# HealthMonitor.net
KiCad netlist of a schematic drawn in EAGLE
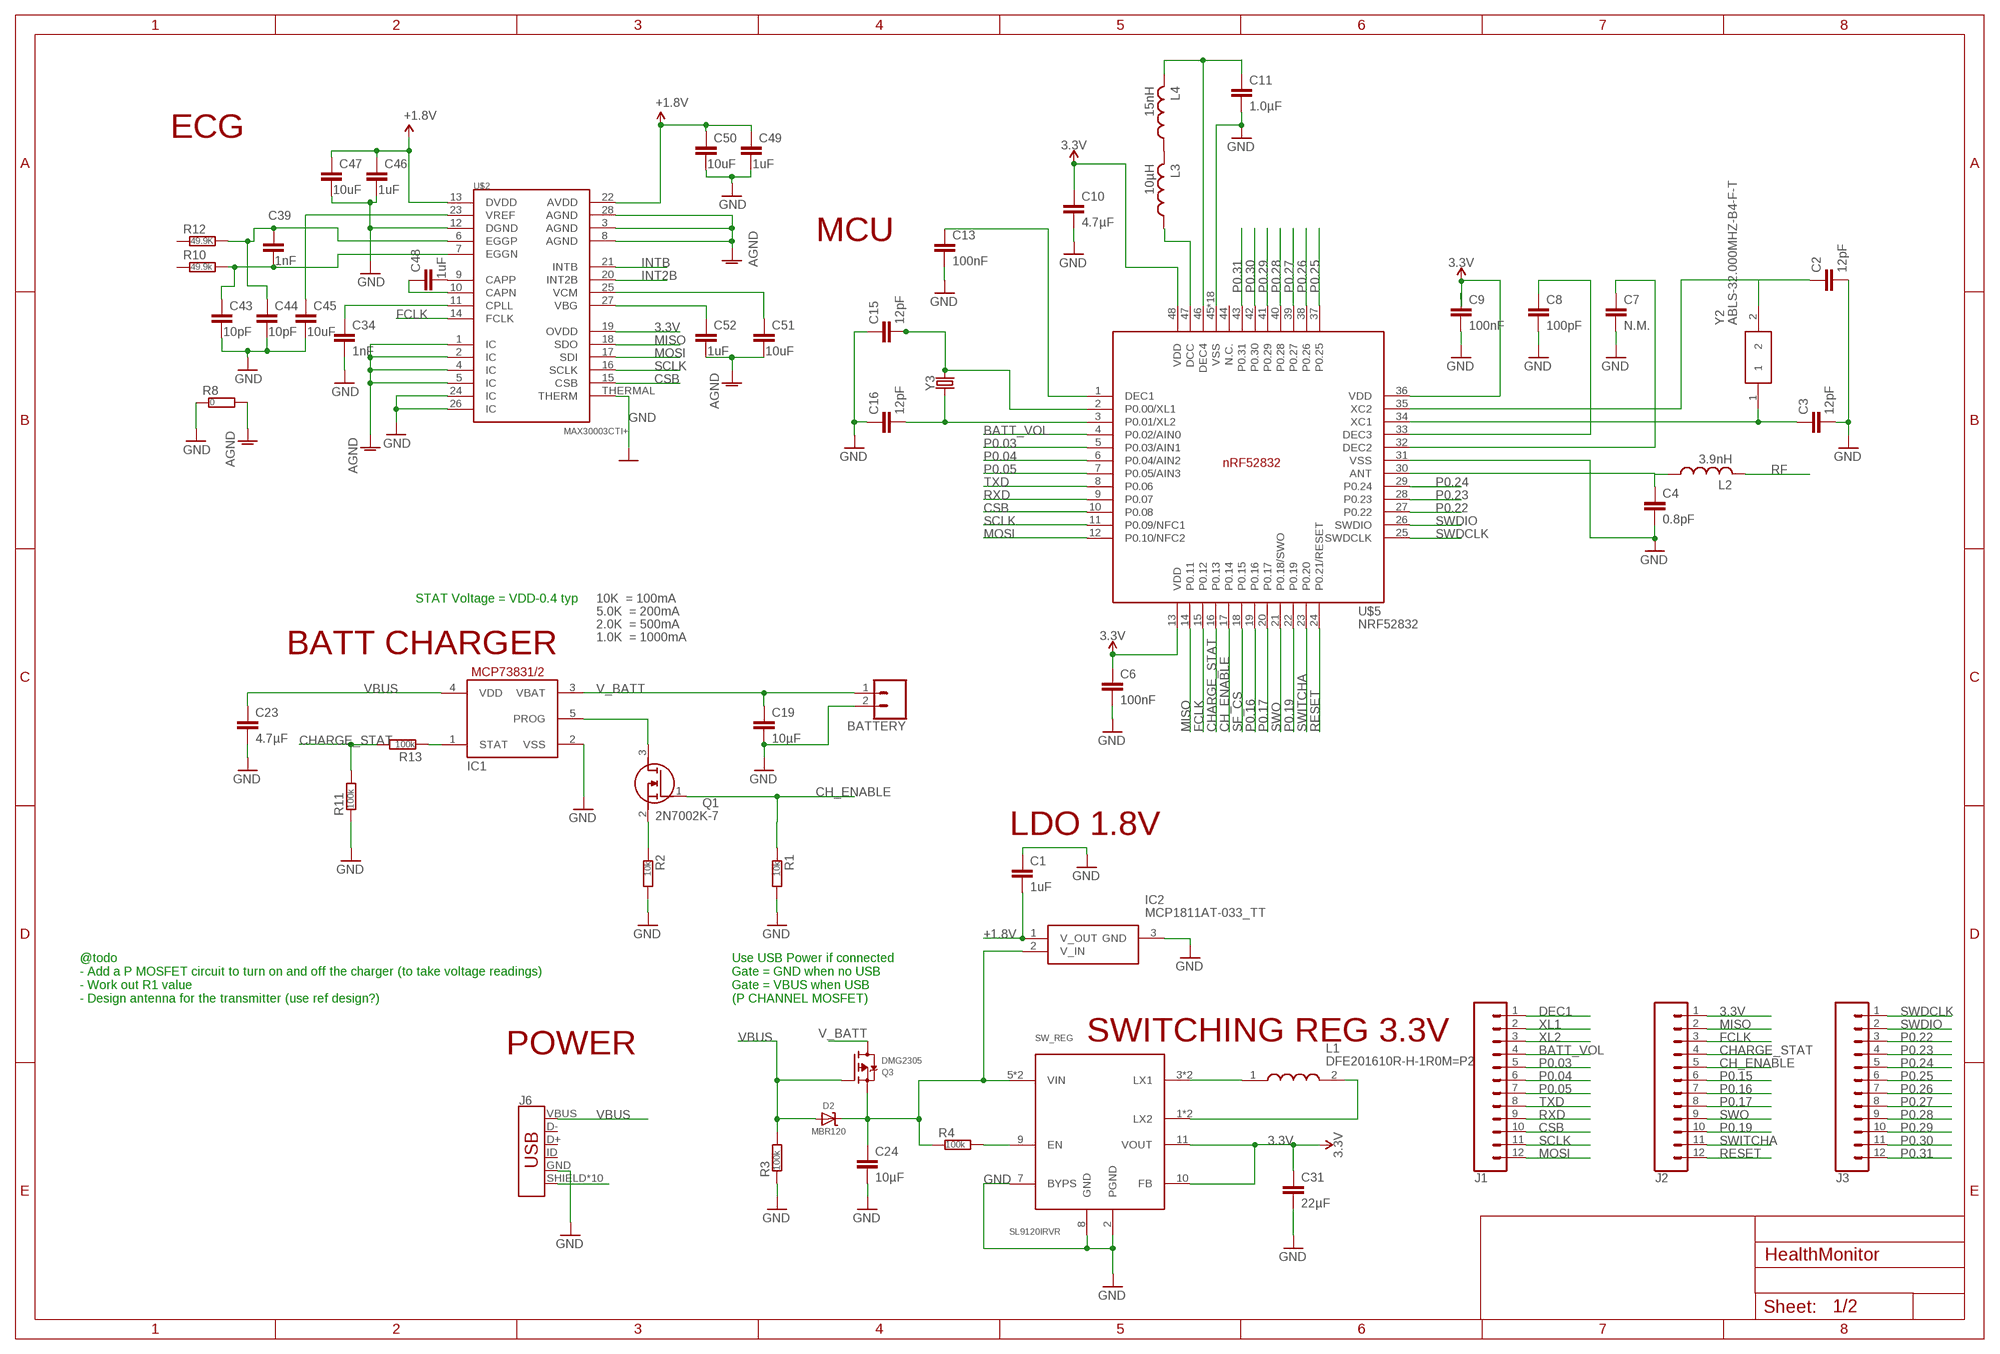
[diagram p0: schematic, sheet 1]
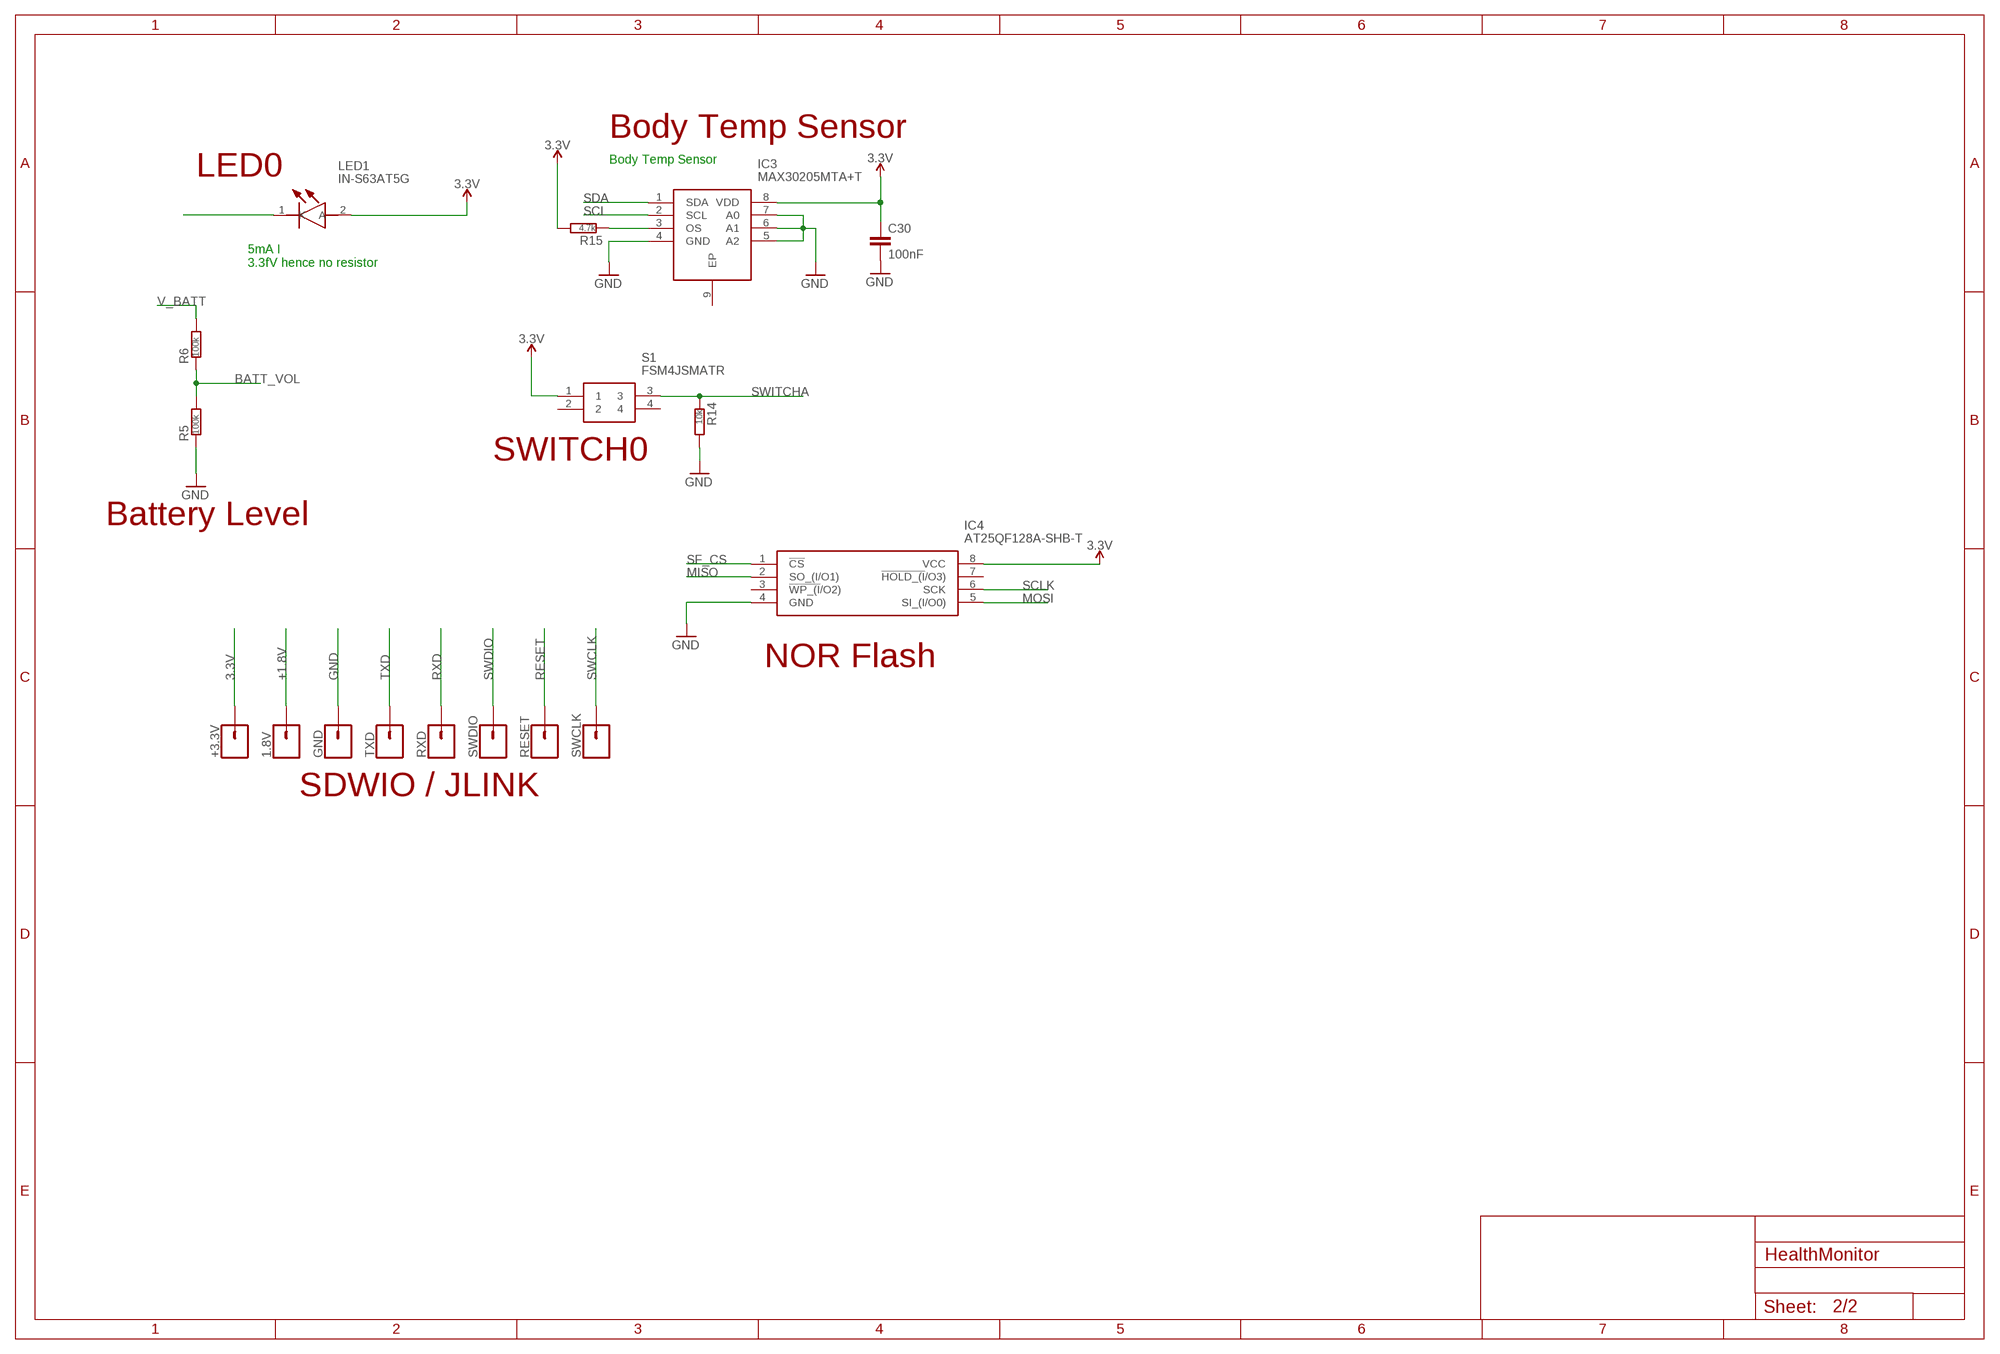
[diagram p1: schematic, sheet 2]

(export (version "E")
  (design (tool "Eeschema 10.0.6"))
  (components
    (comp (ref "BATTERY")
      (value "CONN_02")
      (footprint "eagle-import:1X02")
      (libsource (lib "eagle-import") (part "CONN_02"))
    )
    (comp (ref "C1")
      (value "1uF")
      (footprint "eagle-import:RESC0603_L")
      (libsource (lib "eagle-import") (part "CAPACITOR_0603_L"))
    )
    (comp (ref "C2")
      (value "12pF")
      (footprint "eagle-import:RESC0603_L")
      (libsource (lib "eagle-import") (part "CAPACITOR_0603_L"))
    )
    (comp (ref "C3")
      (value "12pF")
      (footprint "eagle-import:RESC0603_L")
      (libsource (lib "eagle-import") (part "CAPACITOR_0603_L"))
    )
    (comp (ref "C4")
      (value "0.8pF")
      (footprint "eagle-import:RESC0603_L")
      (libsource (lib "eagle-import") (part "CAPACITOR_0603_L"))
    )
    (comp (ref "C6")
      (value "100nF")
      (footprint "eagle-import:RESC0603_L")
      (libsource (lib "eagle-import") (part "CAPACITOR_0603_L"))
    )
    (comp (ref "C7")
      (value "N.M.")
      (footprint "eagle-import:RESC0603_L")
      (libsource (lib "eagle-import") (part "CAPACITOR_0603_L"))
    )
    (comp (ref "C8")
      (value "100pF")
      (footprint "eagle-import:RESC0603_L")
      (libsource (lib "eagle-import") (part "CAPACITOR_0603_L"))
    )
    (comp (ref "C9")
      (value "100nF")
      (footprint "eagle-import:RESC0603_L")
      (libsource (lib "eagle-import") (part "CAPACITOR_0603_L"))
    )
    (comp (ref "C10")
      (value "4.7µF")
      (footprint "eagle-import:RESC0603_N")
      (libsource (lib "eagle-import") (part "CAPACITOR_0603_N"))
    )
    (comp (ref "C11")
      (value "1.0µF")
      (footprint "eagle-import:RESC0603_N")
      (libsource (lib "eagle-import") (part "CAPACITOR_0603_N"))
    )
    (comp (ref "C13")
      (value "100nF")
      (footprint "eagle-import:RESC0603_L")
      (libsource (lib "eagle-import") (part "CAPACITOR_0603_L"))
    )
    (comp (ref "C15")
      (value "12pF")
      (footprint "eagle-import:RESC0603_L")
      (libsource (lib "eagle-import") (part "CAPACITOR_0603_L"))
    )
    (comp (ref "C16")
      (value "12pF")
      (footprint "eagle-import:RESC0603_L")
      (libsource (lib "eagle-import") (part "CAPACITOR_0603_L"))
    )
    (comp (ref "C19")
      (value "10µF")
      (footprint "eagle-import:RESC0603_N")
      (libsource (lib "eagle-import") (part "CAPACITOR_0603_N"))
    )
    (comp (ref "C23")
      (value "4.7µF")
      (footprint "eagle-import:RESC0603_N")
      (libsource (lib "eagle-import") (part "CAPACITOR_0603_N"))
    )
    (comp (ref "C24")
      (value "10µF")
      (footprint "eagle-import:RESC0603_N")
      (libsource (lib "eagle-import") (part "CAPACITOR_0603_N"))
    )
    (comp (ref "C31")
      (value "22µF")
      (footprint "eagle-import:RESC0603_N")
      (libsource (lib "eagle-import") (part "CAPACITOR_0603_N"))
    )
    (comp (ref "C34")
      (value "1nF")
      (footprint "eagle-import:C0603")
      (libsource (lib "eagle-import") (part "C-EUC0603"))
    )
    (comp (ref "C39")
      (value "1nF")
      (footprint "eagle-import:RESC0603_N")
      (libsource (lib "eagle-import") (part "CAPACITOR_0603_N"))
    )
    (comp (ref "C43")
      (value "10pF")
      (footprint "eagle-import:RESC0603_N")
      (libsource (lib "eagle-import") (part "CAPACITOR_0603_N"))
    )
    (comp (ref "C44")
      (value "10pF")
      (footprint "eagle-import:RESC0603_N")
      (libsource (lib "eagle-import") (part "CAPACITOR_0603_N"))
    )
    (comp (ref "C45")
      (value "10uF")
      (footprint "eagle-import:RESC0603_N")
      (libsource (lib "eagle-import") (part "CAPACITOR_0603_N"))
    )
    (comp (ref "C46")
      (value "1uF")
      (footprint "eagle-import:RESC0603_N")
      (libsource (lib "eagle-import") (part "CAPACITOR_0603_N"))
    )
    (comp (ref "C47")
      (value "10uF")
      (footprint "eagle-import:RESC0603_N")
      (libsource (lib "eagle-import") (part "CAPACITOR_0603_N"))
    )
    (comp (ref "C48")
      (value "1uF")
      (footprint "eagle-import:RESC0603_N")
      (libsource (lib "eagle-import") (part "CAPACITOR_0603_N"))
    )
    (comp (ref "C49")
      (value "1uF")
      (footprint "eagle-import:RESC0603_N")
      (libsource (lib "eagle-import") (part "CAPACITOR_0603_N"))
    )
    (comp (ref "C50")
      (value "10uF")
      (footprint "eagle-import:RESC0603_N")
      (libsource (lib "eagle-import") (part "CAPACITOR_0603_N"))
    )
    (comp (ref "C51")
      (value "10uF")
      (footprint "eagle-import:RESC0603_N")
      (libsource (lib "eagle-import") (part "CAPACITOR_0603_N"))
    )
    (comp (ref "C52")
      (value "1uF")
      (footprint "eagle-import:RESC0603_N")
      (libsource (lib "eagle-import") (part "CAPACITOR_0603_N"))
    )
    (comp (ref "D2")
      (value "MBR120")
      (footprint "eagle-import:SOD-123")
      (libsource (lib "eagle-import") (part "DIODE-SCHOTTKYSOD-123"))
    )
    (comp (ref "IC1")
      (value "MCP73831/OT")
      (footprint "eagle-import:SOT23-5L")
      (libsource (lib "eagle-import") (part "MCP73831/OT"))
    )
    (comp (ref "IC2")
      (value "MCP1811AT-033_TT")
      (footprint "eagle-import:SOT95P237X112-3N")
      (fields
        (field (name "MANUFACTURER_PART_NUMBER") "MCP1811AT-033/TT")
        (field (name "MOUSER_PART_NUMBER") "579-MCP1811AT-033/TT")
      )
      (libsource (lib "eagle-import") (part "MCP1811AT-033_TT"))
    )
    (comp (ref "J1")
      (value "CONN_12")
      (footprint "eagle-import:1X12")
      (libsource (lib "eagle-import") (part "CONN_12"))
    )
    (comp (ref "J2")
      (value "CONN_12")
      (footprint "eagle-import:1X12")
      (libsource (lib "eagle-import") (part "CONN_12"))
    )
    (comp (ref "J3")
      (value "CONN_12")
      (footprint "eagle-import:1X12")
      (libsource (lib "eagle-import") (part "CONN_12"))
    )
    (comp (ref "J6")
      (value "USB_MICRO-B_HALF_PTH_MILL")
      (footprint "eagle-import:USB-MICROB-PTH-MILL")
      (libsource (lib "eagle-import") (part "USB_MICRO-B_HALF_PTH_MILL"))
    )
    (comp (ref "L1")
      (value "DFE201610R-H-1R0M=P2")
      (footprint "eagle-import:INDC2016X100N")
      (fields (field (name "MOUSER_PART_NUMBER") "81-DFE201610RH1R0MP2"))
      (libsource (lib "eagle-import") (part "DFE201610R-H-1R0M=P2"))
    )
    (comp (ref "L2")
      (value "3.9nH")
      (footprint "eagle-import:RESC0402_N")
      (libsource (lib "eagle-import") (part "INDUCTOR_0402_N"))
    )
    (comp (ref "L3")
      (value "10µH")
      (footprint "eagle-import:RESC0603_N")
      (libsource (lib "eagle-import") (part "INDUCTOR_0603_N"))
    )
    (comp (ref "L4")
      (value "15nH")
      (footprint "eagle-import:RESC0402_N")
      (libsource (lib "eagle-import") (part "INDUCTOR_0402_N"))
    )
    (comp (ref "Q1")
      (value "2N7002K-7")
      (footprint "eagle-import:SOT96P240X100-3N")
      (fields (field (name "MOUSER_PART_NUMBER") "621-2N7002K-7") (field (name "RS_PART_NUMBER") "7703383"))
      (libsource (lib "eagle-import") (part "2N7002K-7"))
    )
    (comp (ref "Q3")
      (value "DMG2305")
      (footprint "eagle-import:SOT23-R")
      (libsource (lib "eagle-import") (part "MOSFET-P"))
    )
    (comp (ref "R1")
      (value "10k")
      (footprint "eagle-import:RESC0603_L")
      (libsource (lib "eagle-import") (part "RESISTOR_0603_L"))
    )
    (comp (ref "R2")
      (value "10k")
      (footprint "eagle-import:RESC0603_L")
      (libsource (lib "eagle-import") (part "RESISTOR_0603_L"))
    )
    (comp (ref "R3")
      (value "100k")
      (footprint "eagle-import:RESC0603_L")
      (libsource (lib "eagle-import") (part "RESISTOR_0603_L"))
    )
    (comp (ref "R4")
      (value "100k")
      (footprint "eagle-import:RESC0603_L")
      (libsource (lib "eagle-import") (part "RESISTOR_0603_L"))
    )
    (comp (ref "R8")
      (value "0")
      (footprint "eagle-import:RESC0603_L")
      (libsource (lib "eagle-import") (part "RESISTOR_0603_L"))
    )
    (comp (ref "R10")
      (value "49.9k")
      (footprint "eagle-import:RESC0603_L")
      (libsource (lib "eagle-import") (part "RESISTOR_0603_L"))
    )
    (comp (ref "R11")
      (value "100k")
      (footprint "eagle-import:RESC0603_L")
      (libsource (lib "eagle-import") (part "RESISTOR_0603_L"))
    )
    (comp (ref "R12")
      (value "49.9K")
      (footprint "eagle-import:RESC0603_L")
      (libsource (lib "eagle-import") (part "RESISTOR_0603_L"))
    )
    (comp (ref "R13")
      (value "100k")
      (footprint "eagle-import:RESC0603_L")
      (libsource (lib "eagle-import") (part "RESISTOR_0603_L"))
    )
    (comp (ref "SW_REG")
      (value "SL9120IRVR")
      (footprint "eagle-import:TQFN-12")
      (libsource (lib "eagle-import") (part "SL9120IRVR"))
    )
    (comp (ref "U$2")
      (value "MAX30003CTI+")
      (footprint "eagle-import:QFN-28")
      (libsource (lib "eagle-import") (part "MAX30003"))
    )
    (comp (ref "U$5")
      (value "NRF52832")
      (footprint "eagle-import:QFN40P600X600X90-48_N")
      (libsource (lib "eagle-import") (part "NRF52832"))
    )
    (comp (ref "Y2")
      (value "ABLS-32.000MHZ-B4-F-T")
      (footprint "eagle-import:ABLS-12.000MHZ-B2")
      (fields (field (name "MOUSER_PART_NUMBER") "815-ABLS-32.0MF-T"))
      (libsource (lib "eagle-import") (part "ABLS-32.000MHZ-B4-F-T"))
    )
    (comp (ref "Y3")
      (value "CRYSTALSMD-2X6")
      (footprint "eagle-import:CRYSTAL-SMD-2X6-CYL")
      (libsource (lib "eagle-import") (part "CRYSTALSMD-2X6"))
    )
    (comp (ref "+3.3V")
      (value "CONN_01")
      (footprint "eagle-import:1X01")
      (libsource (lib "eagle-import") (part "CONN_01"))
    )
    (comp (ref "1.8V")
      (value "CONN_01")
      (footprint "eagle-import:1X01")
      (libsource (lib "eagle-import") (part "CONN_01"))
    )
    (comp (ref "C30")
      (value "100nF")
      (footprint "eagle-import:RESC0603_L")
      (libsource (lib "eagle-import") (part "CAPACITOR_0603_L"))
    )
    (comp (ref "GND")
      (value "CONN_01")
      (footprint "eagle-import:1X01")
      (libsource (lib "eagle-import") (part "CONN_01"))
    )
    (comp (ref "IC3")
      (value "MAX30205MTA+T")
      (footprint "eagle-import:SON65P300X300X80-9N")
      (fields (field (name "MOUSER_PART_NUMBER") "700-MAX30205MTA+T"))
      (libsource (lib "eagle-import") (part "MAX30205MTA+T"))
    )
    (comp (ref "IC4")
      (value "AT25QF128A-SHB-T")
      (footprint "eagle-import:SOIC127P790X216-8N")
      (fields (field (name "MOUSER_PART_NUMBER") "988-AT25QF128A-SHB-T"))
      (libsource (lib "eagle-import") (part "AT25QF128A-SHB-T"))
    )
    (comp (ref "LED1")
      (value "IN-S63AT5G")
      (footprint "eagle-import:LEDM168X39N")
      (fields (field (name "MOUSER_PART_NUMBER") "743-IN-S63AT5G"))
      (libsource (lib "eagle-import") (part "IN-S63AT5G"))
    )
    (comp (ref "R5")
      (value "100k")
      (footprint "eagle-import:RESC0603_L")
      (libsource (lib "eagle-import") (part "RESISTOR_0603_L"))
    )
    (comp (ref "R6")
      (value "100k")
      (footprint "eagle-import:RESC0603_L")
      (libsource (lib "eagle-import") (part "RESISTOR_0603_L"))
    )
    (comp (ref "R14")
      (value "10k")
      (footprint "eagle-import:RESC0603_L")
      (libsource (lib "eagle-import") (part "RESISTOR_0603_L"))
    )
    (comp (ref "R15")
      (value "4.7k")
      (footprint "eagle-import:RESC0603_L")
      (libsource (lib "eagle-import") (part "RESISTOR_0603_L"))
    )
    (comp (ref "RESET")
      (value "CONN_01")
      (footprint "eagle-import:1X01")
      (libsource (lib "eagle-import") (part "CONN_01"))
    )
    (comp (ref "RXD")
      (value "CONN_01")
      (footprint "eagle-import:1X01")
      (libsource (lib "eagle-import") (part "CONN_01"))
    )
    (comp (ref "S1")
      (value "FSM4JSMATR")
      (footprint "eagle-import:FSM4JSMATR")
      (fields (field (name "MOUSER_PART_NUMBER") "506-FSM4JSMATR") (field (name "RS_PART_NUMBER") "7182455P"))
      (libsource (lib "eagle-import") (part "FSM4JSMATR"))
    )
    (comp (ref "SWCLK")
      (value "CONN_01")
      (footprint "eagle-import:1X01")
      (libsource (lib "eagle-import") (part "CONN_01"))
    )
    (comp (ref "SWDIO")
      (value "CONN_01")
      (footprint "eagle-import:1X01")
      (libsource (lib "eagle-import") (part "CONN_01"))
    )
    (comp (ref "TXD")
      (value "CONN_01")
      (footprint "eagle-import:1X01")
      (libsource (lib "eagle-import") (part "CONN_01"))
    )
  )
  (nets
    (net (code "1") (name "+1.8V") (class "Default")
      (node (ref "1.8V") (pin "1") (pinfunction "1_1") (pintype "passive"))
      (node (ref "C1") (pin "2") (pinfunction "2_2") (pintype "passive"))
      (node (ref "C46") (pin "1") (pinfunction "1_1") (pintype "passive"))
      (node (ref "C47") (pin "1") (pinfunction "1_1") (pintype "passive"))
      (node (ref "C49") (pin "1") (pinfunction "1_1") (pintype "passive"))
      (node (ref "C50") (pin "1") (pinfunction "1_1") (pintype "passive"))
      (node (ref "IC2") (pin "1") (pinfunction "V_OUT_1") (pintype "bidirectional"))
      (node (ref "U$2") (pin "13") (pinfunction "DVDD_13") (pintype "bidirectional"))
      (node (ref "U$2") (pin "22") (pinfunction "AVDD_22") (pintype "bidirectional"))
    )
    (net (code "2") (name "3.3V") (class "Default")
      (node (ref "+3.3V") (pin "1") (pinfunction "1_1") (pintype "passive"))
      (node (ref "C10") (pin "1") (pinfunction "1_1") (pintype "passive"))
      (node (ref "C30") (pin "1") (pinfunction "1_1") (pintype "passive"))
      (node (ref "C31") (pin "1") (pinfunction "1_1") (pintype "passive"))
      (node (ref "C6") (pin "1") (pinfunction "1_1") (pintype "passive"))
      (node (ref "C9") (pin "1") (pinfunction "1_1") (pintype "passive"))
      (node (ref "IC3") (pin "8") (pinfunction "VDD_8") (pintype "bidirectional"))
      (node (ref "IC4") (pin "8") (pinfunction "VCC_8") (pintype "bidirectional"))
      (node (ref "J2") (pin "1") (pinfunction "1_1") (pintype "passive"))
      (node (ref "LED1") (pin "2") (pinfunction "A_2") (pintype "bidirectional"))
      (node (ref "R15") (pin "2") (pinfunction "2_2") (pintype "passive"))
      (node (ref "S1") (pin "1") (pinfunction "1_1") (pintype "bidirectional"))
      (node (ref "SW_REG") (pin "10") (pinfunction "FB_10") (pintype "bidirectional"))
      (node (ref "SW_REG") (pin "11") (pinfunction "VOUT_11") (pintype "bidirectional"))
      (node (ref "U$2") (pin "19") (pinfunction "OVDD_19") (pintype "bidirectional"))
      (node (ref "U$5") (pin "13") (pinfunction "VDD_13") (pintype "power_in"))
      (node (ref "U$5") (pin "36") (pinfunction "VDD_36") (pintype "power_in"))
      (node (ref "U$5") (pin "48") (pinfunction "VDD_48") (pintype "power_in"))
    )
    (net (code "3") (name "AGND") (class "Default")
      (node (ref "C51") (pin "2") (pinfunction "2_2") (pintype "passive"))
      (node (ref "C52") (pin "2") (pinfunction "2_2") (pintype "passive"))
      (node (ref "R8") (pin "2") (pinfunction "2_2") (pintype "passive"))
      (node (ref "U$2") (pin "1") (pinfunction "IC_1") (pintype "bidirectional"))
      (node (ref "U$2") (pin "2") (pinfunction "IC_2") (pintype "bidirectional"))
      (node (ref "U$2") (pin "28") (pinfunction "AGND_28") (pintype "bidirectional"))
      (node (ref "U$2") (pin "3") (pinfunction "AGND_3") (pintype "bidirectional"))
      (node (ref "U$2") (pin "4") (pinfunction "IC_4") (pintype "bidirectional"))
      (node (ref "U$2") (pin "5") (pinfunction "IC_5") (pintype "bidirectional"))
      (node (ref "U$2") (pin "8") (pinfunction "AGND_8") (pintype "bidirectional"))
    )
    (net (code "4") (name "BATT_VOL") (class "Default")
      (node (ref "J1") (pin "4") (pinfunction "4_4") (pintype "passive"))
      (node (ref "R5") (pin "2") (pinfunction "2_2") (pintype "passive"))
      (node (ref "R6") (pin "1") (pinfunction "1_1") (pintype "passive"))
      (node (ref "U$5") (pin "4") (pinfunction "P0.02/AIN0_4") (pintype "bidirectional"))
    )
    (net (code "5") (name "CHARGE_STAT") (class "Default")
      (node (ref "J2") (pin "4") (pinfunction "4_4") (pintype "passive"))
      (node (ref "R11") (pin "2") (pinfunction "2_2") (pintype "passive"))
      (node (ref "R13") (pin "2") (pinfunction "2_2") (pintype "passive"))
      (node (ref "U$5") (pin "16") (pinfunction "P0.13_16") (pintype "bidirectional"))
    )
    (net (code "6") (name "CH_ENABLE") (class "Default")
      (node (ref "J2") (pin "5") (pinfunction "5_5") (pintype "passive"))
      (node (ref "Q1") (pin "1") (pinfunction "G_1") (pintype "bidirectional"))
      (node (ref "R1") (pin "1") (pinfunction "1_1") (pintype "passive"))
      (node (ref "U$5") (pin "17") (pinfunction "P0.14_17") (pintype "bidirectional"))
    )
    (net (code "7") (name "CSB") (class "Default")
      (node (ref "J1") (pin "10") (pinfunction "10_10") (pintype "passive"))
      (node (ref "U$2") (pin "15") (pinfunction "CSB_15") (pintype "bidirectional"))
      (node (ref "U$5") (pin "10") (pinfunction "P0.08_10") (pintype "bidirectional"))
    )
    (net (code "8") (name "DEC1") (class "Default")
      (node (ref "J1") (pin "1") (pinfunction "1_1") (pintype "passive"))
    )
    (net (code "9") (name "FCLK") (class "Default")
      (node (ref "J2") (pin "3") (pinfunction "3_3") (pintype "passive"))
      (node (ref "U$2") (pin "14") (pinfunction "FCLK_14") (pintype "bidirectional"))
      (node (ref "U$5") (pin "15") (pinfunction "P0.12_15") (pintype "bidirectional"))
    )
    (net (code "10") (name "GND") (class "Default")
      (node (ref "BATTERY") (pin "2") (pinfunction "2_2") (pintype "passive"))
      (node (ref "C1") (pin "1") (pinfunction "1_1") (pintype "passive"))
      (node (ref "C10") (pin "2") (pinfunction "2_2") (pintype "passive"))
      (node (ref "C11") (pin "2") (pinfunction "2_2") (pintype "passive"))
      (node (ref "C13") (pin "2") (pinfunction "2_2") (pintype "passive"))
      (node (ref "C15") (pin "1") (pinfunction "1_1") (pintype "passive"))
      (node (ref "C16") (pin "1") (pinfunction "1_1") (pintype "passive"))
      (node (ref "C19") (pin "2") (pinfunction "2_2") (pintype "passive"))
      (node (ref "C2") (pin "2") (pinfunction "2_2") (pintype "passive"))
      (node (ref "C23") (pin "2") (pinfunction "2_2") (pintype "passive"))
      (node (ref "C24") (pin "2") (pinfunction "2_2") (pintype "passive"))
      (node (ref "C3") (pin "2") (pinfunction "2_2") (pintype "passive"))
      (node (ref "C30") (pin "2") (pinfunction "2_2") (pintype "passive"))
      (node (ref "C31") (pin "2") (pinfunction "2_2") (pintype "passive"))
      (node (ref "C34") (pin "2") (pinfunction "2_2") (pintype "passive"))
      (node (ref "C4") (pin "2") (pinfunction "2_2") (pintype "passive"))
      (node (ref "C43") (pin "2") (pinfunction "2_2") (pintype "passive"))
      (node (ref "C44") (pin "2") (pinfunction "2_2") (pintype "passive"))
      (node (ref "C45") (pin "2") (pinfunction "2_2") (pintype "passive"))
      (node (ref "C46") (pin "2") (pinfunction "2_2") (pintype "passive"))
      (node (ref "C47") (pin "2") (pinfunction "2_2") (pintype "passive"))
      (node (ref "C49") (pin "2") (pinfunction "2_2") (pintype "passive"))
      (node (ref "C50") (pin "2") (pinfunction "2_2") (pintype "passive"))
      (node (ref "C6") (pin "2") (pinfunction "2_2") (pintype "passive"))
      (node (ref "C7") (pin "2") (pinfunction "2_2") (pintype "passive"))
      (node (ref "C8") (pin "2") (pinfunction "2_2") (pintype "passive"))
      (node (ref "C9") (pin "2") (pinfunction "2_2") (pintype "passive"))
      (node (ref "GND") (pin "1") (pinfunction "1_1") (pintype "passive"))
      (node (ref "IC1") (pin "2") (pinfunction "VSS_2") (pintype "power_in"))
      (node (ref "IC2") (pin "3") (pinfunction "GND_3") (pintype "bidirectional"))
      (node (ref "IC3") (pin "4") (pinfunction "GND_4") (pintype "bidirectional"))
      (node (ref "IC3") (pin "5") (pinfunction "A2_5") (pintype "bidirectional"))
      (node (ref "IC3") (pin "6") (pinfunction "A1_6") (pintype "bidirectional"))
      (node (ref "IC3") (pin "7") (pinfunction "A0_7") (pintype "bidirectional"))
      (node (ref "IC4") (pin "4") (pinfunction "GND_4") (pintype "bidirectional"))
      (node (ref "J6") (pin "GND") (pinfunction "GND_GND") (pintype "power_in"))
      (node (ref "R1") (pin "2") (pinfunction "2_2") (pintype "passive"))
      (node (ref "R11") (pin "1") (pinfunction "1_1") (pintype "passive"))
      (node (ref "R14") (pin "2") (pinfunction "2_2") (pintype "passive"))
      (node (ref "R2") (pin "2") (pinfunction "2_2") (pintype "passive"))
      (node (ref "R3") (pin "1") (pinfunction "1_1") (pintype "passive"))
      (node (ref "R5") (pin "1") (pinfunction "1_1") (pintype "passive"))
      (node (ref "R8") (pin "1") (pinfunction "1_1") (pintype "passive"))
      (node (ref "SW_REG") (pin "2") (pinfunction "PGND_2") (pintype "bidirectional"))
      (node (ref "SW_REG") (pin "7") (pinfunction "BYPS_7") (pintype "bidirectional"))
      (node (ref "SW_REG") (pin "8") (pinfunction "GND_8") (pintype "bidirectional"))
      (node (ref "U$2") (pin "12") (pinfunction "DGND_12") (pintype "bidirectional"))
      (node (ref "U$2") (pin "24") (pinfunction "IC_24") (pintype "bidirectional"))
      (node (ref "U$2") (pin "26") (pinfunction "IC_26") (pintype "bidirectional"))
      (node (ref "U$2") (pin "THERMAL") (pinfunction "THERM_THERMAL") (pintype "bidirectional"))
      (node (ref "U$5") (pin "31") (pinfunction "VSS_31") (pintype "bidirectional"))
      (node (ref "U$5") (pin "45") (pinfunction "VSS_45") (pintype "power_in"))
      (node (ref "U$5") (pin "PAD") (pinfunction "VSS_PAD") (pintype "power_in"))
      (node (ref "U$5") (pin "PAD@VIA01") (pinfunction "VSS_PAD@VIA01") (pintype "power_in"))
      (node (ref "U$5") (pin "PAD@VIA02") (pinfunction "VSS_PAD@VIA02") (pintype "power_in"))
      (node (ref "U$5") (pin "PAD@VIA03") (pinfunction "VSS_PAD@VIA03") (pintype "power_in"))
      (node (ref "U$5") (pin "PAD@VIA04") (pinfunction "VSS_PAD@VIA04") (pintype "power_in"))
      (node (ref "U$5") (pin "PAD@VIA05") (pinfunction "VSS_PAD@VIA05") (pintype "power_in"))
      (node (ref "U$5") (pin "PAD@VIA06") (pinfunction "VSS_PAD@VIA06") (pintype "power_in"))
      (node (ref "U$5") (pin "PAD@VIA07") (pinfunction "VSS_PAD@VIA07") (pintype "power_in"))
      (node (ref "U$5") (pin "PAD@VIA08") (pinfunction "VSS_PAD@VIA08") (pintype "power_in"))
      (node (ref "U$5") (pin "PAD@VIA09") (pinfunction "VSS_PAD@VIA09") (pintype "power_in"))
      (node (ref "U$5") (pin "PAD@VIA10") (pinfunction "VSS_PAD@VIA10") (pintype "power_in"))
      (node (ref "U$5") (pin "PAD@VIA11") (pinfunction "VSS_PAD@VIA11") (pintype "power_in"))
      (node (ref "U$5") (pin "PAD@VIA12") (pinfunction "VSS_PAD@VIA12") (pintype "power_in"))
      (node (ref "U$5") (pin "PAD@VIA13") (pinfunction "VSS_PAD@VIA13") (pintype "power_in"))
      (node (ref "U$5") (pin "PAD@VIA14") (pinfunction "VSS_PAD@VIA14") (pintype "power_in"))
      (node (ref "U$5") (pin "PAD@VIA15") (pinfunction "VSS_PAD@VIA15") (pintype "power_in"))
      (node (ref "U$5") (pin "PAD@VIA16") (pinfunction "VSS_PAD@VIA16") (pintype "power_in"))
    )
    (net (code "11") (name "INT2B") (class "Default")
      (node (ref "U$2") (pin "20") (pinfunction "INT2B_20") (pintype "bidirectional"))
    )
    (net (code "12") (name "INTB") (class "Default")
      (node (ref "U$2") (pin "21") (pinfunction "INTB_21") (pintype "bidirectional"))
    )
    (net (code "13") (name "MISO") (class "Default")
      (node (ref "IC4") (pin "2") (pinfunction "SO_(I/O1)_2") (pintype "bidirectional"))
      (node (ref "J2") (pin "2") (pinfunction "2_2") (pintype "passive"))
      (node (ref "U$2") (pin "18") (pinfunction "SDO_18") (pintype "bidirectional"))
      (node (ref "U$5") (pin "14") (pinfunction "P0.11_14") (pintype "bidirectional"))
    )
    (net (code "14") (name "MOSI") (class "Default")
      (node (ref "IC4") (pin "5") (pinfunction "SI_(I/O0)_5") (pintype "bidirectional"))
      (node (ref "J1") (pin "12") (pinfunction "12_12") (pintype "passive"))
      (node (ref "U$2") (pin "17") (pinfunction "SDI_17") (pintype "bidirectional"))
      (node (ref "U$5") (pin "12") (pinfunction "P0.10/NFC2_12") (pintype "bidirectional"))
    )
    (net (code "15") (name "Net-(C2-Pad1)") (class "Default")
      (node (ref "C2") (pin "1") (pinfunction "1_1") (pintype "passive"))
      (node (ref "Y2") (pin "2") (pinfunction "2_2") (pintype "bidirectional"))
    )
    (net (code "16") (name "Net-(C4-Pad1)") (class "Default")
      (node (ref "C4") (pin "1") (pinfunction "1_1") (pintype "passive"))
      (node (ref "L2") (pin "1") (pinfunction "1_1") (pintype "passive"))
    )
    (net (code "17") (name "Net-(IC1-PROG)") (class "Default")
      (node (ref "IC1") (pin "5") (pinfunction "PROG_5") (pintype "input"))
      (node (ref "Q1") (pin "3") (pinfunction "D_3") (pintype "bidirectional"))
    )
    (net (code "18") (name "Net-(IC1-STAT)") (class "Default")
      (node (ref "IC1") (pin "1") (pinfunction "STAT_1") (pintype "output"))
      (node (ref "R13") (pin "1") (pinfunction "1_1") (pintype "passive"))
    )
    (net (code "19") (name "Net-(IC2-V_IN)") (class "Default")
      (node (ref "C24") (pin "1") (pinfunction "1_1") (pintype "passive"))
      (node (ref "D2") (pin "C") (pinfunction "C_C") (pintype "passive"))
      (node (ref "IC2") (pin "2") (pinfunction "V_IN_2") (pintype "bidirectional"))
      (node (ref "Q3") (pin "2") (pinfunction "S_2") (pintype "passive"))
      (node (ref "R4") (pin "1") (pinfunction "1_1") (pintype "passive"))
      (node (ref "SW_REG") (pin "5") (pinfunction "VIN_5") (pintype "bidirectional"))
      (node (ref "SW_REG") (pin "6") (pinfunction "VIN_6") (pintype "bidirectional"))
    )
    (net (code "20") (name "Net-(IC3-OS)") (class "Default")
      (node (ref "IC3") (pin "3") (pinfunction "OS_3") (pintype "bidirectional"))
      (node (ref "R15") (pin "1") (pinfunction "1_1") (pintype "passive"))
    )
    (net (code "21") (name "Net-(J6-PadSHIELD)") (class "Default")
      (node (ref "J6") (pin "SHIELD") (pinfunction "SHIELD_SHIELD") (pintype "bidirectional"))
      (node (ref "J6") (pin "SHIELD10") (pinfunction "SHIELD_SHIELD10") (pintype "bidirectional"))
      (node (ref "J6") (pin "SHIELD2") (pinfunction "SHIELD_SHIELD2") (pintype "bidirectional"))
      (node (ref "J6") (pin "SHIELD3") (pinfunction "SHIELD_SHIELD3") (pintype "bidirectional"))
      (node (ref "J6") (pin "SHIELD4") (pinfunction "SHIELD_SHIELD4") (pintype "bidirectional"))
      (node (ref "J6") (pin "SHIELD5") (pinfunction "SHIELD_SHIELD5") (pintype "bidirectional"))
      (node (ref "J6") (pin "SHIELD6") (pinfunction "SHIELD_SHIELD6") (pintype "bidirectional"))
      (node (ref "J6") (pin "SHIELD7") (pinfunction "SHIELD_SHIELD7") (pintype "bidirectional"))
      (node (ref "J6") (pin "SHIELD8") (pinfunction "SHIELD_SHIELD8") (pintype "bidirectional"))
      (node (ref "J6") (pin "SHIELD9") (pinfunction "SHIELD_SHIELD9") (pintype "bidirectional"))
    )
    (net (code "22") (name "Net-(L1-Pad1)") (class "Default")
      (node (ref "L1") (pin "1") (pinfunction "1_1") (pintype "bidirectional"))
      (node (ref "SW_REG") (pin "3") (pinfunction "LX1_3") (pintype "bidirectional"))
      (node (ref "SW_REG") (pin "4") (pinfunction "LX1_4") (pintype "bidirectional"))
    )
    (net (code "23") (name "Net-(L1-Pad2)") (class "Default")
      (node (ref "L1") (pin "2") (pinfunction "2_2") (pintype "bidirectional"))
      (node (ref "SW_REG") (pin "1") (pinfunction "LX2_1") (pintype "bidirectional"))
      (node (ref "SW_REG") (pin "12") (pinfunction "LX2_12") (pintype "bidirectional"))
    )
    (net (code "24") (name "Net-(L3-Pad2)") (class "Default")
      (node (ref "L3") (pin "2") (pinfunction "2_2") (pintype "passive"))
      (node (ref "L4") (pin "1") (pinfunction "1_1") (pintype "passive"))
    )
    (net (code "25") (name "Net-(Q1-S)") (class "Default")
      (node (ref "Q1") (pin "2") (pinfunction "S_2") (pintype "bidirectional"))
      (node (ref "R2") (pin "1") (pinfunction "1_1") (pintype "passive"))
    )
    (net (code "26") (name "Net-(SW_REG-EN)") (class "Default")
      (node (ref "R4") (pin "2") (pinfunction "2_2") (pintype "passive"))
      (node (ref "SW_REG") (pin "9") (pinfunction "EN_9") (pintype "bidirectional"))
    )
    (net (code "27") (name "Net-(U$2-CAPN)") (class "Default")
      (node (ref "C48") (pin "1") (pinfunction "1_1") (pintype "passive"))
      (node (ref "U$2") (pin "10") (pinfunction "CAPN_10") (pintype "bidirectional"))
    )
    (net (code "28") (name "Net-(U$2-CAPP)") (class "Default")
      (node (ref "C48") (pin "2") (pinfunction "2_2") (pintype "passive"))
      (node (ref "U$2") (pin "9") (pinfunction "CAPP_9") (pintype "bidirectional"))
    )
    (net (code "29") (name "Net-(U$2-CPLL)") (class "Default")
      (node (ref "C34") (pin "1") (pinfunction "1_1") (pintype "passive"))
      (node (ref "U$2") (pin "11") (pinfunction "CPLL_11") (pintype "bidirectional"))
    )
    (net (code "30") (name "Net-(U$2-EGGN)") (class "Default")
      (node (ref "C39") (pin "2") (pinfunction "2_2") (pintype "passive"))
      (node (ref "C43") (pin "1") (pinfunction "1_1") (pintype "passive"))
      (node (ref "R10") (pin "2") (pinfunction "2_2") (pintype "passive"))
      (node (ref "U$2") (pin "7") (pinfunction "EGGN_7") (pintype "bidirectional"))
    )
    (net (code "31") (name "Net-(U$2-EGGP)") (class "Default")
      (node (ref "C39") (pin "1") (pinfunction "1_1") (pintype "passive"))
      (node (ref "C44") (pin "1") (pinfunction "1_1") (pintype "passive"))
      (node (ref "R12") (pin "2") (pinfunction "2_2") (pintype "passive"))
      (node (ref "U$2") (pin "6") (pinfunction "EGGP_6") (pintype "bidirectional"))
    )
    (net (code "32") (name "Net-(U$2-VBG)") (class "Default")
      (node (ref "C52") (pin "1") (pinfunction "1_1") (pintype "passive"))
      (node (ref "U$2") (pin "27") (pinfunction "VBG_27") (pintype "bidirectional"))
    )
    (net (code "33") (name "Net-(U$2-VCM)") (class "Default")
      (node (ref "C51") (pin "1") (pinfunction "1_1") (pintype "passive"))
      (node (ref "U$2") (pin "25") (pinfunction "VCM_25") (pintype "bidirectional"))
    )
    (net (code "34") (name "Net-(U$2-VREF)") (class "Default")
      (node (ref "C45") (pin "1") (pinfunction "1_1") (pintype "passive"))
      (node (ref "U$2") (pin "23") (pinfunction "VREF_23") (pintype "bidirectional"))
    )
    (net (code "35") (name "Net-(U$5-DCC)") (class "Default")
      (node (ref "L3") (pin "1") (pinfunction "1_1") (pintype "passive"))
      (node (ref "U$5") (pin "47") (pinfunction "DCC_47") (pintype "output"))
    )
    (net (code "36") (name "Net-(U$5-DEC1)") (class "Default")
      (node (ref "C13") (pin "1") (pinfunction "1_1") (pintype "passive"))
      (node (ref "U$5") (pin "1") (pinfunction "DEC1_1") (pintype "power_in"))
    )
    (net (code "37") (name "Net-(U$5-DEC2)") (class "Default")
      (node (ref "C7") (pin "1") (pinfunction "1_1") (pintype "passive"))
      (node (ref "U$5") (pin "32") (pinfunction "DEC2_32") (pintype "bidirectional"))
    )
    (net (code "38") (name "Net-(U$5-DEC3)") (class "Default")
      (node (ref "C8") (pin "1") (pinfunction "1_1") (pintype "passive"))
      (node (ref "U$5") (pin "33") (pinfunction "DEC3_33") (pintype "bidirectional"))
    )
    (net (code "39") (name "Net-(U$5-DEC4)") (class "Default")
      (node (ref "C11") (pin "1") (pinfunction "1_1") (pintype "passive"))
      (node (ref "L4") (pin "2") (pinfunction "2_2") (pintype "passive"))
      (node (ref "U$5") (pin "46") (pinfunction "DEC4_46") (pintype "power_in"))
    )
    (net (code "40") (name "Net-(U$5-P0.01{slash}XL2)") (class "Default")
      (node (ref "C16") (pin "2") (pinfunction "2_2") (pintype "passive"))
      (node (ref "U$5") (pin "3") (pinfunction "P0.01/XL2_3") (pintype "bidirectional"))
      (node (ref "Y3") (pin "X1") (pinfunction "1_X1") (pintype "passive"))
    )
    (net (code "41") (name "Net-(U$5-XC1)") (class "Default")
      (node (ref "C3") (pin "1") (pinfunction "1_1") (pintype "passive"))
      (node (ref "U$5") (pin "34") (pinfunction "XC1_34") (pintype "input"))
      (node (ref "Y2") (pin "1") (pinfunction "1_1") (pintype "bidirectional"))
    )
    (net (code "42") (name "P0.03") (class "Default")
      (node (ref "J1") (pin "5") (pinfunction "5_5") (pintype "passive"))
      (node (ref "U$5") (pin "5") (pinfunction "P0.03/AIN1_5") (pintype "bidirectional"))
    )
    (net (code "43") (name "P0.04") (class "Default")
      (node (ref "J1") (pin "6") (pinfunction "6_6") (pintype "passive"))
      (node (ref "U$5") (pin "6") (pinfunction "P0.04/AIN2_6") (pintype "bidirectional"))
    )
    (net (code "44") (name "P0.05") (class "Default")
      (node (ref "J1") (pin "7") (pinfunction "7_7") (pintype "passive"))
      (node (ref "U$5") (pin "7") (pinfunction "P0.05/AIN3_7") (pintype "bidirectional"))
    )
    (net (code "45") (name "P0.15") (class "Default")
      (node (ref "J2") (pin "6") (pinfunction "6_6") (pintype "passive"))
    )
    (net (code "46") (name "P0.16") (class "Default")
      (node (ref "J2") (pin "7") (pinfunction "7_7") (pintype "passive"))
      (node (ref "U$5") (pin "19") (pinfunction "P0.16_19") (pintype "bidirectional"))
    )
    (net (code "47") (name "P0.17") (class "Default")
      (node (ref "J2") (pin "8") (pinfunction "8_8") (pintype "passive"))
      (node (ref "U$5") (pin "20") (pinfunction "P0.17_20") (pintype "bidirectional"))
    )
    (net (code "48") (name "P0.19") (class "Default")
      (node (ref "J2") (pin "10") (pinfunction "10_10") (pintype "passive"))
      (node (ref "U$5") (pin "22") (pinfunction "P0.19_22") (pintype "bidirectional"))
    )
    (net (code "49") (name "P0.22") (class "Default")
      (node (ref "J3") (pin "3") (pinfunction "3_3") (pintype "passive"))
      (node (ref "U$5") (pin "27") (pinfunction "P0.22_27") (pintype "bidirectional"))
    )
    (net (code "50") (name "P0.23") (class "Default")
      (node (ref "J3") (pin "4") (pinfunction "4_4") (pintype "passive"))
      (node (ref "U$5") (pin "28") (pinfunction "P0.23_28") (pintype "bidirectional"))
    )
    (net (code "51") (name "P0.24") (class "Default")
      (node (ref "J3") (pin "5") (pinfunction "5_5") (pintype "passive"))
      (node (ref "U$5") (pin "29") (pinfunction "P0.24_29") (pintype "bidirectional"))
    )
    (net (code "52") (name "P0.25") (class "Default")
      (node (ref "J3") (pin "6") (pinfunction "6_6") (pintype "passive"))
      (node (ref "U$5") (pin "37") (pinfunction "P0.25_37") (pintype "bidirectional"))
    )
    (net (code "53") (name "P0.26") (class "Default")
      (node (ref "J3") (pin "7") (pinfunction "7_7") (pintype "passive"))
      (node (ref "U$5") (pin "38") (pinfunction "P0.26_38") (pintype "bidirectional"))
    )
    (net (code "54") (name "P0.27") (class "Default")
      (node (ref "J3") (pin "8") (pinfunction "8_8") (pintype "passive"))
      (node (ref "U$5") (pin "39") (pinfunction "P0.27_39") (pintype "bidirectional"))
    )
    (net (code "55") (name "P0.28") (class "Default")
      (node (ref "J3") (pin "9") (pinfunction "9_9") (pintype "passive"))
      (node (ref "U$5") (pin "40") (pinfunction "P0.28_40") (pintype "bidirectional"))
    )
    (net (code "56") (name "P0.29") (class "Default")
      (node (ref "J3") (pin "10") (pinfunction "10_10") (pintype "passive"))
      (node (ref "U$5") (pin "41") (pinfunction "P0.29_41") (pintype "bidirectional"))
    )
    (net (code "57") (name "P0.30") (class "Default")
      (node (ref "J3") (pin "11") (pinfunction "11_11") (pintype "passive"))
      (node (ref "U$5") (pin "42") (pinfunction "P0.30_42") (pintype "bidirectional"))
    )
    (net (code "58") (name "P0.31") (class "Default")
      (node (ref "J3") (pin "12") (pinfunction "12_12") (pintype "passive"))
      (node (ref "U$5") (pin "43") (pinfunction "P0.31_43") (pintype "bidirectional"))
    )
    (net (code "59") (name "RESET") (class "Default")
      (node (ref "J2") (pin "12") (pinfunction "12_12") (pintype "passive"))
      (node (ref "RESET") (pin "1") (pinfunction "1_1") (pintype "passive"))
      (node (ref "U$5") (pin "24") (pinfunction "P0.21/RESET_24") (pintype "bidirectional"))
    )
    (net (code "60") (name "RF") (class "Default")
      (node (ref "L2") (pin "2") (pinfunction "2_2") (pintype "passive"))
    )
    (net (code "61") (name "RXD") (class "Default")
      (node (ref "J1") (pin "9") (pinfunction "9_9") (pintype "passive"))
      (node (ref "RXD") (pin "1") (pinfunction "1_1") (pintype "passive"))
      (node (ref "U$5") (pin "9") (pinfunction "P0.07_9") (pintype "bidirectional"))
    )
    (net (code "62") (name "SCL") (class "Default")
      (node (ref "IC3") (pin "2") (pinfunction "SCL_2") (pintype "bidirectional"))
    )
    (net (code "63") (name "SCLK") (class "Default")
      (node (ref "IC4") (pin "6") (pinfunction "SCK_6") (pintype "bidirectional"))
      (node (ref "J1") (pin "11") (pinfunction "11_11") (pintype "passive"))
      (node (ref "U$2") (pin "16") (pinfunction "SCLK_16") (pintype "bidirectional"))
      (node (ref "U$5") (pin "11") (pinfunction "P0.09/NFC1_11") (pintype "bidirectional"))
    )
    (net (code "64") (name "SDA") (class "Default")
      (node (ref "IC3") (pin "1") (pinfunction "SDA_1") (pintype "bidirectional"))
    )
    (net (code "65") (name "SF_CS") (class "Default")
      (node (ref "IC4") (pin "1") (pinfunction "~{CS}_1") (pintype "bidirectional"))
      (node (ref "U$5") (pin "18") (pinfunction "P0.15_18") (pintype "bidirectional"))
    )
    (net (code "66") (name "SWCLK") (class "Default")
      (node (ref "SWCLK") (pin "1") (pinfunction "1_1") (pintype "passive"))
    )
    (net (code "67") (name "SWDCLK") (class "Default")
      (node (ref "J3") (pin "1") (pinfunction "1_1") (pintype "passive"))
      (node (ref "U$5") (pin "25") (pinfunction "SWDCLK_25") (pintype "input"))
    )
    (net (code "68") (name "SWDIO") (class "Default")
      (node (ref "J3") (pin "2") (pinfunction "2_2") (pintype "passive"))
      (node (ref "SWDIO") (pin "1") (pinfunction "1_1") (pintype "passive"))
      (node (ref "U$5") (pin "26") (pinfunction "SWDIO_26") (pintype "bidirectional"))
    )
    (net (code "69") (name "SWITCHA") (class "Default")
      (node (ref "J2") (pin "11") (pinfunction "11_11") (pintype "passive"))
      (node (ref "R14") (pin "1") (pinfunction "1_1") (pintype "passive"))
      (node (ref "S1") (pin "3") (pinfunction "3_3") (pintype "bidirectional"))
      (node (ref "U$5") (pin "23") (pinfunction "P0.20_23") (pintype "bidirectional"))
    )
    (net (code "70") (name "SWO") (class "Default")
      (node (ref "J2") (pin "9") (pinfunction "9_9") (pintype "passive"))
      (node (ref "U$5") (pin "21") (pinfunction "P0.18/SWO_21") (pintype "bidirectional"))
    )
    (net (code "71") (name "TXD") (class "Default")
      (node (ref "J1") (pin "8") (pinfunction "8_8") (pintype "passive"))
      (node (ref "TXD") (pin "1") (pinfunction "1_1") (pintype "passive"))
      (node (ref "U$5") (pin "8") (pinfunction "P0.06_8") (pintype "bidirectional"))
    )
    (net (code "72") (name "VBUS") (class "Default")
      (node (ref "C23") (pin "1") (pinfunction "1_1") (pintype "passive"))
      (node (ref "D2") (pin "A") (pinfunction "A_A") (pintype "passive"))
      (node (ref "IC1") (pin "4") (pinfunction "VDD_4") (pintype "power_in"))
      (node (ref "J6") (pin "VBUS") (pinfunction "VBUS_VBUS") (pintype "power_in"))
      (node (ref "Q3") (pin "1") (pinfunction "G_1") (pintype "passive"))
      (node (ref "R3") (pin "2") (pinfunction "2_2") (pintype "passive"))
    )
    (net (code "73") (name "V_BATT") (class "Default")
      (node (ref "BATTERY") (pin "1") (pinfunction "1_1") (pintype "passive"))
      (node (ref "C19") (pin "1") (pinfunction "1_1") (pintype "passive"))
      (node (ref "IC1") (pin "3") (pinfunction "VBAT_3") (pintype "bidirectional"))
      (node (ref "Q3") (pin "3") (pinfunction "D_3") (pintype "passive"))
      (node (ref "R6") (pin "2") (pinfunction "2_2") (pintype "passive"))
    )
    (net (code "74") (name "XL1") (class "Default")
      (node (ref "C15") (pin "2") (pinfunction "2_2") (pintype "passive"))
      (node (ref "J1") (pin "2") (pinfunction "2_2") (pintype "passive"))
      (node (ref "U$5") (pin "2") (pinfunction "P0.00/XL1_2") (pintype "bidirectional"))
      (node (ref "Y3") (pin "X2") (pinfunction "2_X2") (pintype "passive"))
    )
    (net (code "75") (name "XL2") (class "Default")
      (node (ref "J1") (pin "3") (pinfunction "3_3") (pintype "passive"))
    )
    (net (code "76") (name "unconnected-(IC3-EP-Pad9)") (class "Default")
      (node (ref "IC3") (pin "9") (pinfunction "EP_9") (pintype "bidirectional"))
    )
    (net (code "77") (name "unconnected-(IC4-~{HOLD_(I}{slash}O3)-Pad7)") (class "Default")
      (node (ref "IC4") (pin "7") (pinfunction "~{HOLD_(I}/O3)_7") (pintype "bidirectional"))
    )
    (net (code "78") (name "unconnected-(IC4-~{WP_(I}{slash}O2)-Pad3)") (class "Default")
      (node (ref "IC4") (pin "3") (pinfunction "~{WP_(I}/O2)_3") (pintype "bidirectional"))
    )
    (net (code "79") (name "unconnected-(J6-PadD+)") (class "Default")
      (node (ref "J6") (pin "D+") (pinfunction "D+_D+") (pintype "bidirectional"))
    )
    (net (code "80") (name "unconnected-(J6-PadD-)") (class "Default")
      (node (ref "J6") (pin "D-") (pinfunction "D-_D-") (pintype "bidirectional"))
    )
    (net (code "81") (name "unconnected-(J6-PadID)") (class "Default")
      (node (ref "J6") (pin "ID") (pinfunction "ID_ID") (pintype "bidirectional"))
    )
    (net (code "82") (name "unconnected-(LED1-K-Pad1)") (class "Default")
      (node (ref "LED1") (pin "1") (pinfunction "K_1") (pintype "bidirectional"))
    )
    (net (code "83") (name "unconnected-(R10-Pad1)") (class "Default")
      (node (ref "R10") (pin "1") (pinfunction "1_1") (pintype "passive"))
    )
    (net (code "84") (name "unconnected-(R12-Pad1)") (class "Default")
      (node (ref "R12") (pin "1") (pinfunction "1_1") (pintype "passive"))
    )
    (net (code "85") (name "unconnected-(S1-Pad2)") (class "Default")
      (node (ref "S1") (pin "2") (pinfunction "2_2") (pintype "bidirectional"))
    )
    (net (code "86") (name "unconnected-(S1-Pad4)") (class "Default")
      (node (ref "S1") (pin "4") (pinfunction "4_4") (pintype "bidirectional"))
    )
    (net (code "87") (name "unconnected-(U$5-ANT-Pad30)") (class "Default")
      (node (ref "U$5") (pin "30") (pinfunction "ANT_30") (pintype "bidirectional"))
    )
    (net (code "88") (name "unconnected-(U$5-N.C.-Pad44)") (class "Default")
      (node (ref "U$5") (pin "44") (pinfunction "N.C._44") (pintype "no_connect"))
    )
    (net (code "89") (name "unconnected-(U$5-XC2-Pad35)") (class "Default")
      (node (ref "U$5") (pin "35") (pinfunction "XC2_35") (pintype "output"))
    )
  )
)
